# MicroBrute_Noise_add-on.net
KiCad netlist of a schematic drawn in EAGLE
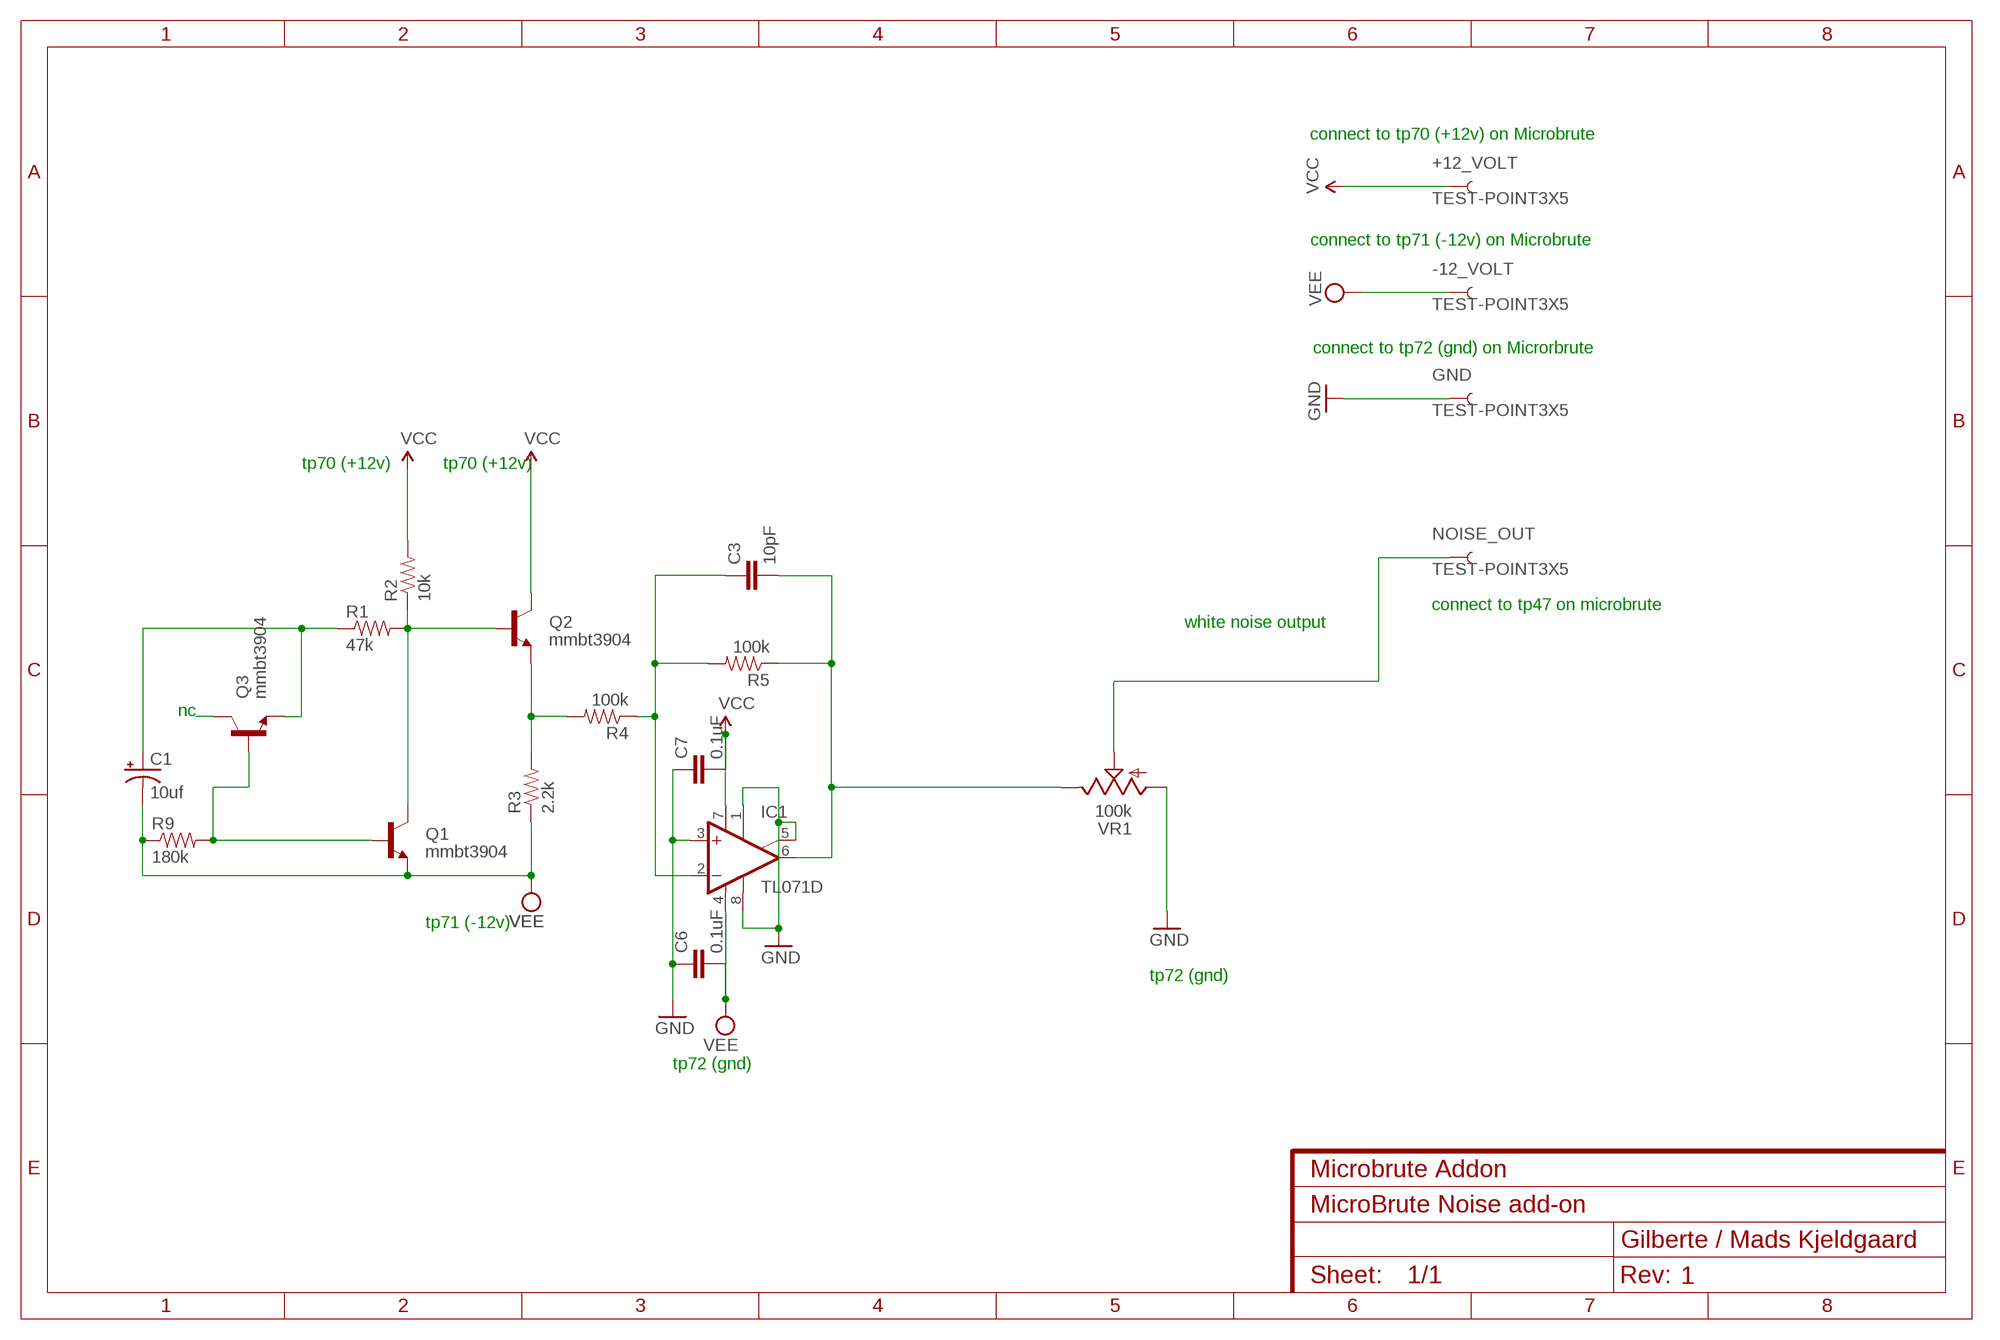
[diagram p0: schematic, sheet 1]

(export (version "E")
  (design (tool "Eeschema 10.0.6"))
  (components
    (comp (ref "+12_VOLT")
      (value "TEST-POINT3X5")
      (footprint "eagle-import:PAD.03X.05")
      (libsource (lib "eagle-import") (part "TEST-POINT3X5"))
    )
    (comp (ref "-12_VOLT")
      (value "TEST-POINT3X5")
      (footprint "eagle-import:PAD.03X.05")
      (libsource (lib "eagle-import") (part "TEST-POINT3X5"))
    )
    (comp (ref "C1")
      (value "10uf")
      (footprint "eagle-import:PANASONIC_C")
      (libsource (lib "eagle-import") (part "CAP_POLC"))
    )
    (comp (ref "C3")
      (value "10pF")
      (footprint "eagle-import:0603-CAP")
      (libsource (lib "eagle-import") (part "0.1UF-25V(+80/-20%)(0603)"))
    )
    (comp (ref "C6")
      (value "0.1uF")
      (footprint "eagle-import:0603-CAP")
      (libsource (lib "eagle-import") (part "0.1UF-25V(+80/-20%)(0603)"))
    )
    (comp (ref "C7")
      (value "0.1uF")
      (footprint "eagle-import:0603-CAP")
      (libsource (lib "eagle-import") (part "0.1UF-25V(+80/-20%)(0603)"))
    )
    (comp (ref "GND")
      (value "TEST-POINT3X5")
      (footprint "eagle-import:PAD.03X.05")
      (libsource (lib "eagle-import") (part "TEST-POINT3X5"))
    )
    (comp (ref "IC1")
      (value "TL071D")
      (footprint "eagle-import:SO08")
      (libsource (lib "eagle-import") (part "TL071D"))
    )
    (comp (ref "NOISE_OUT")
      (value "TEST-POINT3X5")
      (footprint "eagle-import:PAD.03X.05")
      (libsource (lib "eagle-import") (part "TEST-POINT3X5"))
    )
    (comp (ref "Q1")
      (value "mmbt3904")
      (footprint "eagle-import:SOT23-3")
      (libsource (lib "eagle-import") (part "TRANSISTOR_NPNSOT23-3"))
    )
    (comp (ref "Q2")
      (value "mmbt3904")
      (footprint "eagle-import:SOT23-3")
      (libsource (lib "eagle-import") (part "TRANSISTOR_NPNSOT23-3"))
    )
    (comp (ref "Q3")
      (value "mmbt3904")
      (footprint "eagle-import:SOT23-3")
      (libsource (lib "eagle-import") (part "TRANSISTOR_NPNSOT23-3"))
    )
    (comp (ref "R1")
      (value "47k")
      (footprint "eagle-import:0603-RES")
      (libsource (lib "eagle-import") (part "RESISTOR0603-RES"))
    )
    (comp (ref "R2")
      (value "10k")
      (footprint "eagle-import:0603-RES")
      (libsource (lib "eagle-import") (part "RESISTOR0603-RES"))
    )
    (comp (ref "R3")
      (value "2.2k")
      (footprint "eagle-import:0603-RES")
      (libsource (lib "eagle-import") (part "RESISTOR0603-RES"))
    )
    (comp (ref "R4")
      (value "100k")
      (footprint "eagle-import:0603-RES")
      (libsource (lib "eagle-import") (part "RESISTOR0603-RES"))
    )
    (comp (ref "R5")
      (value "100k")
      (footprint "eagle-import:0603-RES")
      (libsource (lib "eagle-import") (part "RESISTOR0603-RES"))
    )
    (comp (ref "R9")
      (value "180k")
      (footprint "eagle-import:0603-RES")
      (libsource (lib "eagle-import") (part "RESISTOR0603-RES"))
    )
    (comp (ref "VR1")
      (value "100k")
      (footprint "eagle-import:9MM_SNAP-IN_POT")
      (libsource (lib "eagle-import") (part "9MM_SNAP-IN_POT_"))
    )
  )
  (nets
    (net (code "1") (name "GND") (class "Default")
      (node (ref "C6") (pin "1") (pinfunction "1_1") (pintype "passive"))
      (node (ref "C7") (pin "1") (pinfunction "1_1") (pintype "passive"))
      (node (ref "GND") (pin "P$1") (pinfunction "1_P$1") (pintype "bidirectional"))
      (node (ref "IC1") (pin "1") (pinfunction "ON1_1") (pintype "passive"))
      (node (ref "IC1") (pin "3") (pinfunction "+IN_3") (pintype "input"))
      (node (ref "IC1") (pin "5") (pinfunction "ON2_5") (pintype "passive"))
      (node (ref "IC1") (pin "8") (pinfunction "OPT_8") (pintype "passive"))
      (node (ref "VR1") (pin "1") (pinfunction "A_1") (pintype "passive"))
    )
    (net (code "2") (name "Net-(IC1--IN)") (class "Default")
      (node (ref "C3") (pin "1") (pinfunction "1_1") (pintype "passive"))
      (node (ref "IC1") (pin "2") (pinfunction "-IN_2") (pintype "input"))
      (node (ref "R4") (pin "1") (pinfunction "1_1") (pintype "passive"))
      (node (ref "R5") (pin "2") (pinfunction "2_2") (pintype "passive"))
    )
    (net (code "3") (name "Net-(IC1-OUT)") (class "Default")
      (node (ref "C3") (pin "2") (pinfunction "2_2") (pintype "passive"))
      (node (ref "IC1") (pin "6") (pinfunction "OUT_6") (pintype "output"))
      (node (ref "R5") (pin "1") (pinfunction "1_1") (pintype "passive"))
      (node (ref "VR1") (pin "3") (pinfunction "E_3") (pintype "passive"))
    )
    (net (code "4") (name "Net-(NOISE_OUT-1)") (class "Default")
      (node (ref "NOISE_OUT") (pin "P$1") (pinfunction "1_P$1") (pintype "bidirectional"))
      (node (ref "VR1") (pin "2") (pinfunction "S_2") (pintype "passive"))
    )
    (net (code "5") (name "Net-(Q1-B)") (class "Default")
      (node (ref "Q1") (pin "1") (pinfunction "B_1") (pintype "passive"))
      (node (ref "Q3") (pin "1") (pinfunction "B_1") (pintype "passive"))
      (node (ref "R9") (pin "2") (pinfunction "2_2") (pintype "passive"))
    )
    (net (code "6") (name "Net-(Q1-C)") (class "Default")
      (node (ref "Q1") (pin "3") (pinfunction "C_3") (pintype "passive"))
      (node (ref "Q2") (pin "1") (pinfunction "B_1") (pintype "passive"))
      (node (ref "R1") (pin "2") (pinfunction "2_2") (pintype "passive"))
      (node (ref "R2") (pin "1") (pinfunction "1_1") (pintype "passive"))
    )
    (net (code "7") (name "Net-(Q2-E)") (class "Default")
      (node (ref "Q2") (pin "2") (pinfunction "E_2") (pintype "passive"))
      (node (ref "R3") (pin "2") (pinfunction "2_2") (pintype "passive"))
      (node (ref "R4") (pin "2") (pinfunction "2_2") (pintype "passive"))
    )
    (net (code "8") (name "Net-(Q3-E)") (class "Default")
      (node (ref "C1") (pin "+") (pinfunction "+_+") (pintype "passive"))
      (node (ref "Q3") (pin "2") (pinfunction "E_2") (pintype "passive"))
      (node (ref "R1") (pin "1") (pinfunction "1_1") (pintype "passive"))
    )
    (net (code "9") (name "VCC") (class "Default")
      (node (ref "+12_VOLT") (pin "P$1") (pinfunction "1_P$1") (pintype "bidirectional"))
      (node (ref "C7") (pin "2") (pinfunction "2_2") (pintype "passive"))
      (node (ref "IC1") (pin "7") (pinfunction "V+_7") (pintype "power_in"))
      (node (ref "Q2") (pin "3") (pinfunction "C_3") (pintype "passive"))
      (node (ref "R2") (pin "2") (pinfunction "2_2") (pintype "passive"))
    )
    (net (code "10") (name "VEE") (class "Default")
      (node (ref "-12_VOLT") (pin "P$1") (pinfunction "1_P$1") (pintype "bidirectional"))
      (node (ref "C1") (pin "-") (pinfunction "-_-") (pintype "passive"))
      (node (ref "C6") (pin "2") (pinfunction "2_2") (pintype "passive"))
      (node (ref "IC1") (pin "4") (pinfunction "V-_4") (pintype "power_in"))
      (node (ref "Q1") (pin "2") (pinfunction "E_2") (pintype "passive"))
      (node (ref "R3") (pin "1") (pinfunction "1_1") (pintype "passive"))
      (node (ref "R9") (pin "1") (pinfunction "1_1") (pintype "passive"))
    )
    (net (code "11") (name "unconnected-(Q3-C-Pad3)") (class "Default")
      (node (ref "Q3") (pin "3") (pinfunction "C_3") (pintype "passive"))
    )
  )
)
